# MyoWare_Proto_Shield.net
KiCad netlist of a schematic drawn in EAGLE
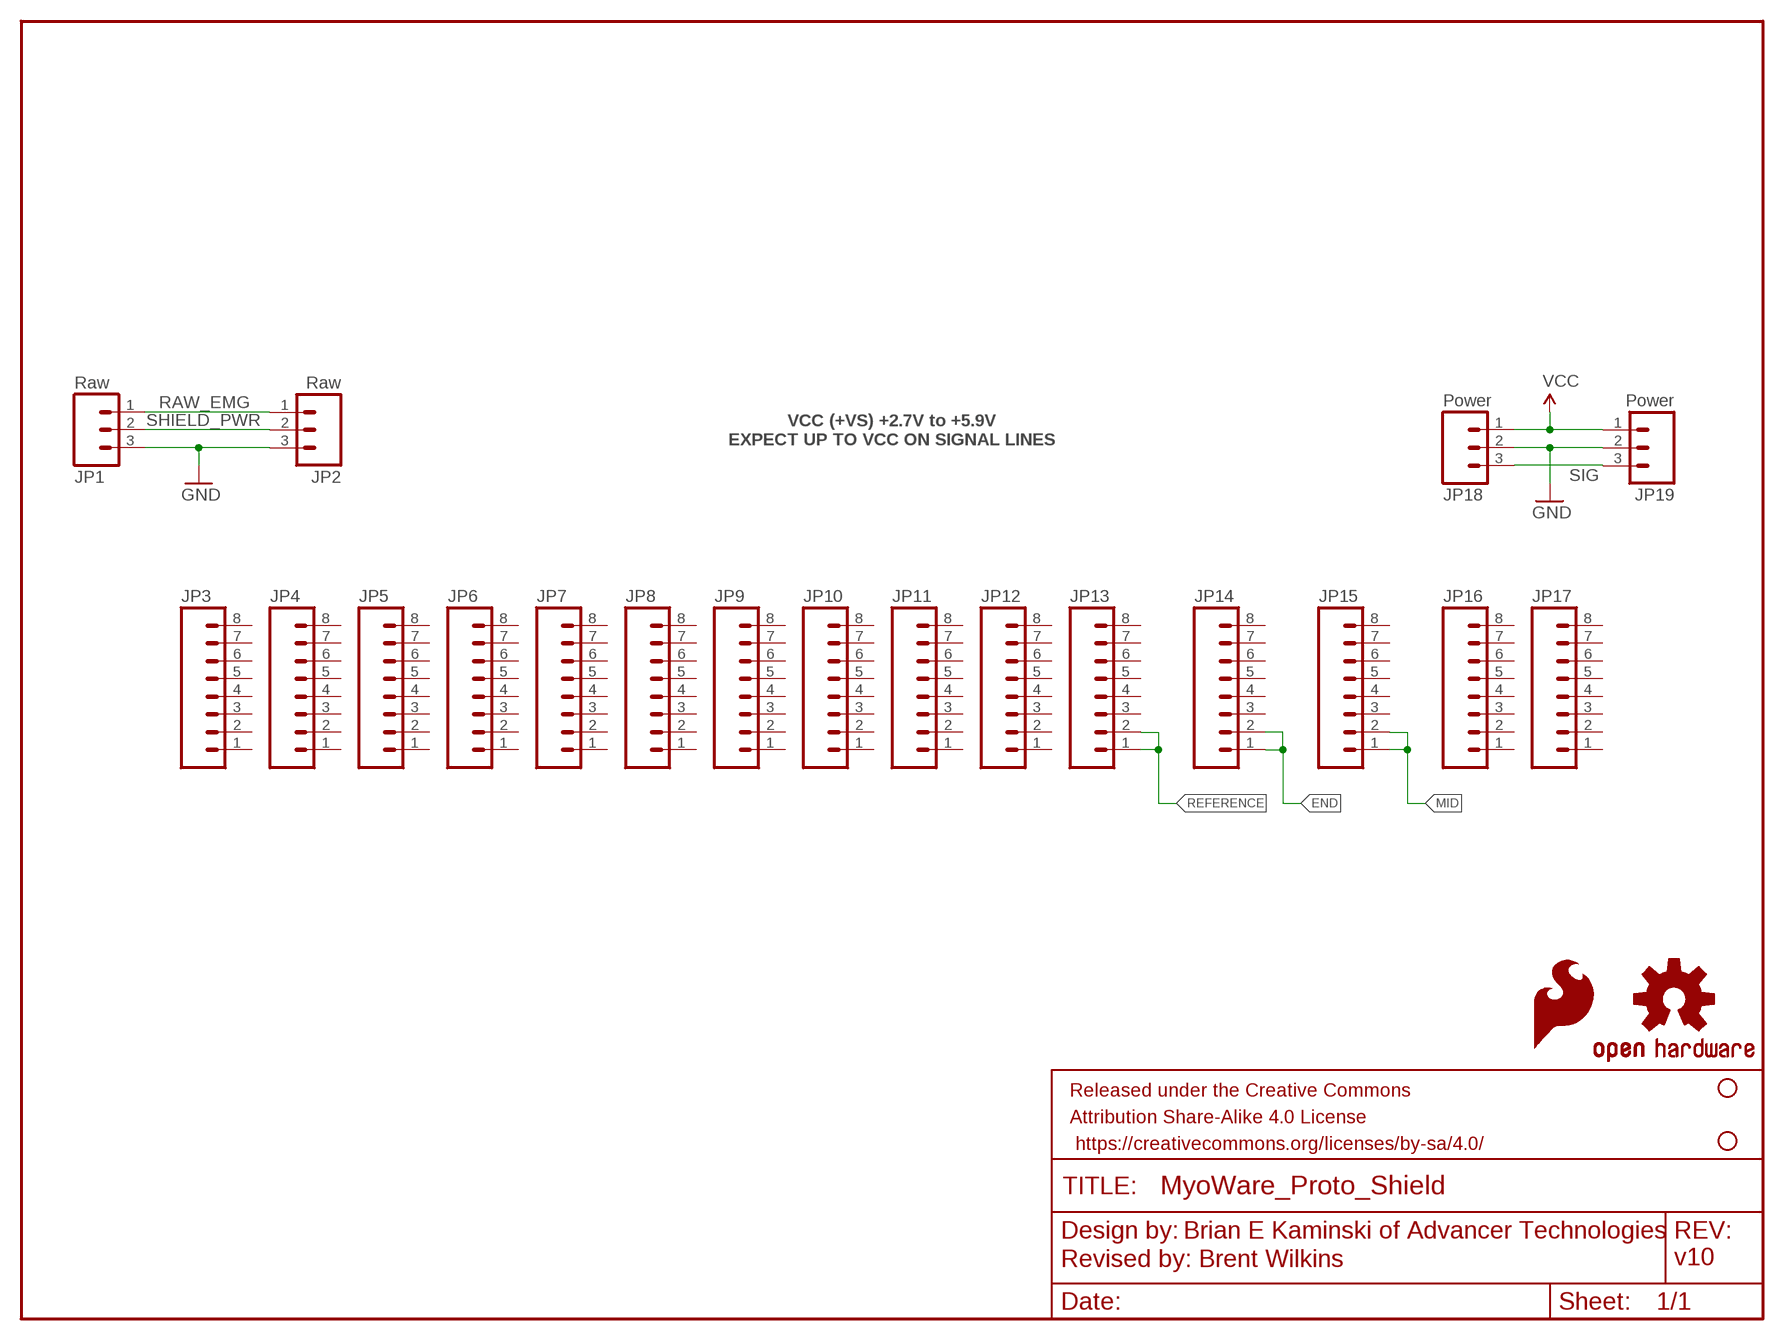
[diagram p0: schematic, sheet 1]

(export (version "E")
  (design (tool "Eeschema 10.0.6"))
  (components
    (comp (ref "FRAME1")
      (value "FRAME-LETTER")
      (footprint "eagle-import:CREATIVE_COMMONS")
      (libsource (lib "eagle-import") (part "FRAME-LETTER"))
    )
    (comp (ref "JP1")
      (value "Raw")
      (footprint "eagle-import:1X03_NO_SILK")
      (libsource (lib "eagle-import") (part "M031X03_NO_SILK"))
    )
    (comp (ref "JP2")
      (value "Raw")
      (footprint "eagle-import:1X03_NO_SILK")
      (libsource (lib "eagle-import") (part "M031X03_NO_SILK"))
    )
    (comp (ref "JP3")
      (value "M08NO_SILK")
      (footprint "eagle-import:1X08_NO_SILK")
      (libsource (lib "eagle-import") (part "M08NO_SILK"))
    )
    (comp (ref "JP4")
      (value "M08NO_SILK")
      (footprint "eagle-import:1X08_NO_SILK")
      (libsource (lib "eagle-import") (part "M08NO_SILK"))
    )
    (comp (ref "JP5")
      (value "M08NO_SILK")
      (footprint "eagle-import:1X08_NO_SILK")
      (libsource (lib "eagle-import") (part "M08NO_SILK"))
    )
    (comp (ref "JP6")
      (value "M08NO_SILK")
      (footprint "eagle-import:1X08_NO_SILK")
      (libsource (lib "eagle-import") (part "M08NO_SILK"))
    )
    (comp (ref "JP7")
      (value "M08NO_SILK")
      (footprint "eagle-import:1X08_NO_SILK")
      (libsource (lib "eagle-import") (part "M08NO_SILK"))
    )
    (comp (ref "JP8")
      (value "M08NO_SILK")
      (footprint "eagle-import:1X08_NO_SILK")
      (libsource (lib "eagle-import") (part "M08NO_SILK"))
    )
    (comp (ref "JP9")
      (value "M08NO_SILK")
      (footprint "eagle-import:1X08_NO_SILK")
      (libsource (lib "eagle-import") (part "M08NO_SILK"))
    )
    (comp (ref "JP10")
      (value "M08NO_SILK")
      (footprint "eagle-import:1X08_NO_SILK")
      (libsource (lib "eagle-import") (part "M08NO_SILK"))
    )
    (comp (ref "JP11")
      (value "M08NO_SILK")
      (footprint "eagle-import:1X08_NO_SILK")
      (libsource (lib "eagle-import") (part "M08NO_SILK"))
    )
    (comp (ref "JP12")
      (value "M08NO_SILK")
      (footprint "eagle-import:1X08_NO_SILK")
      (libsource (lib "eagle-import") (part "M08NO_SILK"))
    )
    (comp (ref "JP13")
      (value "M08NO_SILK")
      (footprint "eagle-import:1X08_NO_SILK")
      (libsource (lib "eagle-import") (part "M08NO_SILK"))
    )
    (comp (ref "JP14")
      (value "M08NO_SILK")
      (footprint "eagle-import:1X08_NO_SILK")
      (libsource (lib "eagle-import") (part "M08NO_SILK"))
    )
    (comp (ref "JP15")
      (value "M08NO_SILK")
      (footprint "eagle-import:1X08_NO_SILK")
      (libsource (lib "eagle-import") (part "M08NO_SILK"))
    )
    (comp (ref "JP16")
      (value "M08NO_SILK")
      (footprint "eagle-import:1X08_NO_SILK")
      (libsource (lib "eagle-import") (part "M08NO_SILK"))
    )
    (comp (ref "JP17")
      (value "M08NO_SILK")
      (footprint "eagle-import:1X08_NO_SILK")
      (libsource (lib "eagle-import") (part "M08NO_SILK"))
    )
    (comp (ref "JP18")
      (value "Power")
      (footprint "eagle-import:1X03_NO_SILK")
      (libsource (lib "eagle-import") (part "M031X03_NO_SILK"))
    )
    (comp (ref "JP19")
      (value "Power")
      (footprint "eagle-import:1X03_NO_SILK")
      (libsource (lib "eagle-import") (part "M031X03_NO_SILK"))
    )
    (comp (ref "JP20")
      (value "STAND-OFF")
      (footprint "eagle-import:STAND-OFF")
      (libsource (lib "eagle-import") (part "STAND-OFF"))
    )
    (comp (ref "JP21")
      (value "STAND-OFF")
      (footprint "eagle-import:STAND-OFF")
      (libsource (lib "eagle-import") (part "STAND-OFF"))
    )
    (comp (ref "LOGO1")
      (value "SFE_LOGO_FLAME.1_INCH")
      (footprint "eagle-import:SFE_LOGO_FLAME_.1")
      (libsource (lib "eagle-import") (part "SFE_LOGO_FLAME.1_INCH"))
    )
    (comp (ref "LOGO2")
      (value "OSHW-LOGOS")
      (footprint "eagle-import:OSHW-LOGO-S")
      (libsource (lib "eagle-import") (part "OSHW-LOGOS"))
    )
  )
  (nets
    (net (code "1") (name "/RAW_EMG") (class "Default")
      (node (ref "JP1") (pin "1") (pinfunction "1_1") (pintype "passive"))
      (node (ref "JP2") (pin "1") (pinfunction "1_1") (pintype "passive"))
    )
    (net (code "2") (name "/SHIELD_PWR") (class "Default")
      (node (ref "JP1") (pin "2") (pinfunction "2_2") (pintype "passive"))
      (node (ref "JP2") (pin "2") (pinfunction "2_2") (pintype "passive"))
    )
    (net (code "3") (name "/SIG") (class "Default")
      (node (ref "JP18") (pin "3") (pinfunction "3_3") (pintype "passive"))
      (node (ref "JP19") (pin "3") (pinfunction "3_3") (pintype "passive"))
    )
    (net (code "4") (name "END") (class "Default")
      (node (ref "JP14") (pin "1") (pinfunction "1_1") (pintype "passive"))
      (node (ref "JP14") (pin "2") (pinfunction "2_2") (pintype "passive"))
    )
    (net (code "5") (name "GND") (class "Default")
      (node (ref "JP1") (pin "3") (pinfunction "3_3") (pintype "passive"))
      (node (ref "JP18") (pin "2") (pinfunction "2_2") (pintype "passive"))
      (node (ref "JP19") (pin "2") (pinfunction "2_2") (pintype "passive"))
      (node (ref "JP2") (pin "3") (pinfunction "3_3") (pintype "passive"))
    )
    (net (code "6") (name "MID") (class "Default")
      (node (ref "JP15") (pin "1") (pinfunction "1_1") (pintype "passive"))
      (node (ref "JP15") (pin "2") (pinfunction "2_2") (pintype "passive"))
    )
    (net (code "7") (name "REFERENCE") (class "Default")
      (node (ref "JP13") (pin "1") (pinfunction "1_1") (pintype "passive"))
      (node (ref "JP13") (pin "2") (pinfunction "2_2") (pintype "passive"))
    )
    (net (code "8") (name "VCC") (class "Default")
      (node (ref "JP18") (pin "1") (pinfunction "1_1") (pintype "passive"))
      (node (ref "JP19") (pin "1") (pinfunction "1_1") (pintype "passive"))
    )
    (net (code "9") (name "unconnected-(JP3-Pad1)") (class "Default")
      (node (ref "JP3") (pin "1") (pinfunction "1_1") (pintype "passive"))
    )
    (net (code "10") (name "unconnected-(JP3-Pad2)") (class "Default")
      (node (ref "JP3") (pin "2") (pinfunction "2_2") (pintype "passive"))
    )
    (net (code "11") (name "unconnected-(JP3-Pad3)") (class "Default")
      (node (ref "JP3") (pin "3") (pinfunction "3_3") (pintype "passive"))
    )
    (net (code "12") (name "unconnected-(JP3-Pad4)") (class "Default")
      (node (ref "JP3") (pin "4") (pinfunction "4_4") (pintype "passive"))
    )
    (net (code "13") (name "unconnected-(JP3-Pad5)") (class "Default")
      (node (ref "JP3") (pin "5") (pinfunction "5_5") (pintype "passive"))
    )
    (net (code "14") (name "unconnected-(JP3-Pad6)") (class "Default")
      (node (ref "JP3") (pin "6") (pinfunction "6_6") (pintype "passive"))
    )
    (net (code "15") (name "unconnected-(JP3-Pad7)") (class "Default")
      (node (ref "JP3") (pin "7") (pinfunction "7_7") (pintype "passive"))
    )
    (net (code "16") (name "unconnected-(JP3-Pad8)") (class "Default")
      (node (ref "JP3") (pin "8") (pinfunction "8_8") (pintype "passive"))
    )
    (net (code "17") (name "unconnected-(JP4-Pad1)") (class "Default")
      (node (ref "JP4") (pin "1") (pinfunction "1_1") (pintype "passive"))
    )
    (net (code "18") (name "unconnected-(JP4-Pad2)") (class "Default")
      (node (ref "JP4") (pin "2") (pinfunction "2_2") (pintype "passive"))
    )
    (net (code "19") (name "unconnected-(JP4-Pad3)") (class "Default")
      (node (ref "JP4") (pin "3") (pinfunction "3_3") (pintype "passive"))
    )
    (net (code "20") (name "unconnected-(JP4-Pad4)") (class "Default")
      (node (ref "JP4") (pin "4") (pinfunction "4_4") (pintype "passive"))
    )
    (net (code "21") (name "unconnected-(JP4-Pad5)") (class "Default")
      (node (ref "JP4") (pin "5") (pinfunction "5_5") (pintype "passive"))
    )
    (net (code "22") (name "unconnected-(JP4-Pad6)") (class "Default")
      (node (ref "JP4") (pin "6") (pinfunction "6_6") (pintype "passive"))
    )
    (net (code "23") (name "unconnected-(JP4-Pad7)") (class "Default")
      (node (ref "JP4") (pin "7") (pinfunction "7_7") (pintype "passive"))
    )
    (net (code "24") (name "unconnected-(JP4-Pad8)") (class "Default")
      (node (ref "JP4") (pin "8") (pinfunction "8_8") (pintype "passive"))
    )
    (net (code "25") (name "unconnected-(JP5-Pad1)") (class "Default")
      (node (ref "JP5") (pin "1") (pinfunction "1_1") (pintype "passive"))
    )
    (net (code "26") (name "unconnected-(JP5-Pad2)") (class "Default")
      (node (ref "JP5") (pin "2") (pinfunction "2_2") (pintype "passive"))
    )
    (net (code "27") (name "unconnected-(JP5-Pad3)") (class "Default")
      (node (ref "JP5") (pin "3") (pinfunction "3_3") (pintype "passive"))
    )
    (net (code "28") (name "unconnected-(JP5-Pad4)") (class "Default")
      (node (ref "JP5") (pin "4") (pinfunction "4_4") (pintype "passive"))
    )
    (net (code "29") (name "unconnected-(JP5-Pad5)") (class "Default")
      (node (ref "JP5") (pin "5") (pinfunction "5_5") (pintype "passive"))
    )
    (net (code "30") (name "unconnected-(JP5-Pad6)") (class "Default")
      (node (ref "JP5") (pin "6") (pinfunction "6_6") (pintype "passive"))
    )
    (net (code "31") (name "unconnected-(JP5-Pad7)") (class "Default")
      (node (ref "JP5") (pin "7") (pinfunction "7_7") (pintype "passive"))
    )
    (net (code "32") (name "unconnected-(JP5-Pad8)") (class "Default")
      (node (ref "JP5") (pin "8") (pinfunction "8_8") (pintype "passive"))
    )
    (net (code "33") (name "unconnected-(JP6-Pad1)") (class "Default")
      (node (ref "JP6") (pin "1") (pinfunction "1_1") (pintype "passive"))
    )
    (net (code "34") (name "unconnected-(JP6-Pad2)") (class "Default")
      (node (ref "JP6") (pin "2") (pinfunction "2_2") (pintype "passive"))
    )
    (net (code "35") (name "unconnected-(JP6-Pad3)") (class "Default")
      (node (ref "JP6") (pin "3") (pinfunction "3_3") (pintype "passive"))
    )
    (net (code "36") (name "unconnected-(JP6-Pad4)") (class "Default")
      (node (ref "JP6") (pin "4") (pinfunction "4_4") (pintype "passive"))
    )
    (net (code "37") (name "unconnected-(JP6-Pad5)") (class "Default")
      (node (ref "JP6") (pin "5") (pinfunction "5_5") (pintype "passive"))
    )
    (net (code "38") (name "unconnected-(JP6-Pad6)") (class "Default")
      (node (ref "JP6") (pin "6") (pinfunction "6_6") (pintype "passive"))
    )
    (net (code "39") (name "unconnected-(JP6-Pad7)") (class "Default")
      (node (ref "JP6") (pin "7") (pinfunction "7_7") (pintype "passive"))
    )
    (net (code "40") (name "unconnected-(JP6-Pad8)") (class "Default")
      (node (ref "JP6") (pin "8") (pinfunction "8_8") (pintype "passive"))
    )
    (net (code "41") (name "unconnected-(JP7-Pad1)") (class "Default")
      (node (ref "JP7") (pin "1") (pinfunction "1_1") (pintype "passive"))
    )
    (net (code "42") (name "unconnected-(JP7-Pad2)") (class "Default")
      (node (ref "JP7") (pin "2") (pinfunction "2_2") (pintype "passive"))
    )
    (net (code "43") (name "unconnected-(JP7-Pad3)") (class "Default")
      (node (ref "JP7") (pin "3") (pinfunction "3_3") (pintype "passive"))
    )
    (net (code "44") (name "unconnected-(JP7-Pad4)") (class "Default")
      (node (ref "JP7") (pin "4") (pinfunction "4_4") (pintype "passive"))
    )
    (net (code "45") (name "unconnected-(JP7-Pad5)") (class "Default")
      (node (ref "JP7") (pin "5") (pinfunction "5_5") (pintype "passive"))
    )
    (net (code "46") (name "unconnected-(JP7-Pad6)") (class "Default")
      (node (ref "JP7") (pin "6") (pinfunction "6_6") (pintype "passive"))
    )
    (net (code "47") (name "unconnected-(JP7-Pad7)") (class "Default")
      (node (ref "JP7") (pin "7") (pinfunction "7_7") (pintype "passive"))
    )
    (net (code "48") (name "unconnected-(JP7-Pad8)") (class "Default")
      (node (ref "JP7") (pin "8") (pinfunction "8_8") (pintype "passive"))
    )
    (net (code "49") (name "unconnected-(JP8-Pad1)") (class "Default")
      (node (ref "JP8") (pin "1") (pinfunction "1_1") (pintype "passive"))
    )
    (net (code "50") (name "unconnected-(JP8-Pad2)") (class "Default")
      (node (ref "JP8") (pin "2") (pinfunction "2_2") (pintype "passive"))
    )
    (net (code "51") (name "unconnected-(JP8-Pad3)") (class "Default")
      (node (ref "JP8") (pin "3") (pinfunction "3_3") (pintype "passive"))
    )
    (net (code "52") (name "unconnected-(JP8-Pad4)") (class "Default")
      (node (ref "JP8") (pin "4") (pinfunction "4_4") (pintype "passive"))
    )
    (net (code "53") (name "unconnected-(JP8-Pad5)") (class "Default")
      (node (ref "JP8") (pin "5") (pinfunction "5_5") (pintype "passive"))
    )
    (net (code "54") (name "unconnected-(JP8-Pad6)") (class "Default")
      (node (ref "JP8") (pin "6") (pinfunction "6_6") (pintype "passive"))
    )
    (net (code "55") (name "unconnected-(JP8-Pad7)") (class "Default")
      (node (ref "JP8") (pin "7") (pinfunction "7_7") (pintype "passive"))
    )
    (net (code "56") (name "unconnected-(JP8-Pad8)") (class "Default")
      (node (ref "JP8") (pin "8") (pinfunction "8_8") (pintype "passive"))
    )
    (net (code "57") (name "unconnected-(JP9-Pad1)") (class "Default")
      (node (ref "JP9") (pin "1") (pinfunction "1_1") (pintype "passive"))
    )
    (net (code "58") (name "unconnected-(JP9-Pad2)") (class "Default")
      (node (ref "JP9") (pin "2") (pinfunction "2_2") (pintype "passive"))
    )
    (net (code "59") (name "unconnected-(JP9-Pad3)") (class "Default")
      (node (ref "JP9") (pin "3") (pinfunction "3_3") (pintype "passive"))
    )
    (net (code "60") (name "unconnected-(JP9-Pad4)") (class "Default")
      (node (ref "JP9") (pin "4") (pinfunction "4_4") (pintype "passive"))
    )
    (net (code "61") (name "unconnected-(JP9-Pad5)") (class "Default")
      (node (ref "JP9") (pin "5") (pinfunction "5_5") (pintype "passive"))
    )
    (net (code "62") (name "unconnected-(JP9-Pad6)") (class "Default")
      (node (ref "JP9") (pin "6") (pinfunction "6_6") (pintype "passive"))
    )
    (net (code "63") (name "unconnected-(JP9-Pad7)") (class "Default")
      (node (ref "JP9") (pin "7") (pinfunction "7_7") (pintype "passive"))
    )
    (net (code "64") (name "unconnected-(JP9-Pad8)") (class "Default")
      (node (ref "JP9") (pin "8") (pinfunction "8_8") (pintype "passive"))
    )
    (net (code "65") (name "unconnected-(JP10-Pad1)") (class "Default")
      (node (ref "JP10") (pin "1") (pinfunction "1_1") (pintype "passive"))
    )
    (net (code "66") (name "unconnected-(JP10-Pad2)") (class "Default")
      (node (ref "JP10") (pin "2") (pinfunction "2_2") (pintype "passive"))
    )
    (net (code "67") (name "unconnected-(JP10-Pad3)") (class "Default")
      (node (ref "JP10") (pin "3") (pinfunction "3_3") (pintype "passive"))
    )
    (net (code "68") (name "unconnected-(JP10-Pad4)") (class "Default")
      (node (ref "JP10") (pin "4") (pinfunction "4_4") (pintype "passive"))
    )
    (net (code "69") (name "unconnected-(JP10-Pad5)") (class "Default")
      (node (ref "JP10") (pin "5") (pinfunction "5_5") (pintype "passive"))
    )
    (net (code "70") (name "unconnected-(JP10-Pad6)") (class "Default")
      (node (ref "JP10") (pin "6") (pinfunction "6_6") (pintype "passive"))
    )
    (net (code "71") (name "unconnected-(JP10-Pad7)") (class "Default")
      (node (ref "JP10") (pin "7") (pinfunction "7_7") (pintype "passive"))
    )
    (net (code "72") (name "unconnected-(JP10-Pad8)") (class "Default")
      (node (ref "JP10") (pin "8") (pinfunction "8_8") (pintype "passive"))
    )
    (net (code "73") (name "unconnected-(JP11-Pad1)") (class "Default")
      (node (ref "JP11") (pin "1") (pinfunction "1_1") (pintype "passive"))
    )
    (net (code "74") (name "unconnected-(JP11-Pad2)") (class "Default")
      (node (ref "JP11") (pin "2") (pinfunction "2_2") (pintype "passive"))
    )
    (net (code "75") (name "unconnected-(JP11-Pad3)") (class "Default")
      (node (ref "JP11") (pin "3") (pinfunction "3_3") (pintype "passive"))
    )
    (net (code "76") (name "unconnected-(JP11-Pad4)") (class "Default")
      (node (ref "JP11") (pin "4") (pinfunction "4_4") (pintype "passive"))
    )
    (net (code "77") (name "unconnected-(JP11-Pad5)") (class "Default")
      (node (ref "JP11") (pin "5") (pinfunction "5_5") (pintype "passive"))
    )
    (net (code "78") (name "unconnected-(JP11-Pad6)") (class "Default")
      (node (ref "JP11") (pin "6") (pinfunction "6_6") (pintype "passive"))
    )
    (net (code "79") (name "unconnected-(JP11-Pad7)") (class "Default")
      (node (ref "JP11") (pin "7") (pinfunction "7_7") (pintype "passive"))
    )
    (net (code "80") (name "unconnected-(JP11-Pad8)") (class "Default")
      (node (ref "JP11") (pin "8") (pinfunction "8_8") (pintype "passive"))
    )
    (net (code "81") (name "unconnected-(JP12-Pad1)") (class "Default")
      (node (ref "JP12") (pin "1") (pinfunction "1_1") (pintype "passive"))
    )
    (net (code "82") (name "unconnected-(JP12-Pad2)") (class "Default")
      (node (ref "JP12") (pin "2") (pinfunction "2_2") (pintype "passive"))
    )
    (net (code "83") (name "unconnected-(JP12-Pad3)") (class "Default")
      (node (ref "JP12") (pin "3") (pinfunction "3_3") (pintype "passive"))
    )
    (net (code "84") (name "unconnected-(JP12-Pad4)") (class "Default")
      (node (ref "JP12") (pin "4") (pinfunction "4_4") (pintype "passive"))
    )
    (net (code "85") (name "unconnected-(JP12-Pad5)") (class "Default")
      (node (ref "JP12") (pin "5") (pinfunction "5_5") (pintype "passive"))
    )
    (net (code "86") (name "unconnected-(JP12-Pad6)") (class "Default")
      (node (ref "JP12") (pin "6") (pinfunction "6_6") (pintype "passive"))
    )
    (net (code "87") (name "unconnected-(JP12-Pad7)") (class "Default")
      (node (ref "JP12") (pin "7") (pinfunction "7_7") (pintype "passive"))
    )
    (net (code "88") (name "unconnected-(JP12-Pad8)") (class "Default")
      (node (ref "JP12") (pin "8") (pinfunction "8_8") (pintype "passive"))
    )
    (net (code "89") (name "unconnected-(JP13-Pad3)") (class "Default")
      (node (ref "JP13") (pin "3") (pinfunction "3_3") (pintype "passive"))
    )
    (net (code "90") (name "unconnected-(JP13-Pad4)") (class "Default")
      (node (ref "JP13") (pin "4") (pinfunction "4_4") (pintype "passive"))
    )
    (net (code "91") (name "unconnected-(JP13-Pad5)") (class "Default")
      (node (ref "JP13") (pin "5") (pinfunction "5_5") (pintype "passive"))
    )
    (net (code "92") (name "unconnected-(JP13-Pad6)") (class "Default")
      (node (ref "JP13") (pin "6") (pinfunction "6_6") (pintype "passive"))
    )
    (net (code "93") (name "unconnected-(JP13-Pad7)") (class "Default")
      (node (ref "JP13") (pin "7") (pinfunction "7_7") (pintype "passive"))
    )
    (net (code "94") (name "unconnected-(JP13-Pad8)") (class "Default")
      (node (ref "JP13") (pin "8") (pinfunction "8_8") (pintype "passive"))
    )
    (net (code "95") (name "unconnected-(JP14-Pad3)") (class "Default")
      (node (ref "JP14") (pin "3") (pinfunction "3_3") (pintype "passive"))
    )
    (net (code "96") (name "unconnected-(JP14-Pad4)") (class "Default")
      (node (ref "JP14") (pin "4") (pinfunction "4_4") (pintype "passive"))
    )
    (net (code "97") (name "unconnected-(JP14-Pad5)") (class "Default")
      (node (ref "JP14") (pin "5") (pinfunction "5_5") (pintype "passive"))
    )
    (net (code "98") (name "unconnected-(JP14-Pad6)") (class "Default")
      (node (ref "JP14") (pin "6") (pinfunction "6_6") (pintype "passive"))
    )
    (net (code "99") (name "unconnected-(JP14-Pad7)") (class "Default")
      (node (ref "JP14") (pin "7") (pinfunction "7_7") (pintype "passive"))
    )
    (net (code "100") (name "unconnected-(JP14-Pad8)") (class "Default")
      (node (ref "JP14") (pin "8") (pinfunction "8_8") (pintype "passive"))
    )
    (net (code "101") (name "unconnected-(JP15-Pad3)") (class "Default")
      (node (ref "JP15") (pin "3") (pinfunction "3_3") (pintype "passive"))
    )
    (net (code "102") (name "unconnected-(JP15-Pad4)") (class "Default")
      (node (ref "JP15") (pin "4") (pinfunction "4_4") (pintype "passive"))
    )
    (net (code "103") (name "unconnected-(JP15-Pad5)") (class "Default")
      (node (ref "JP15") (pin "5") (pinfunction "5_5") (pintype "passive"))
    )
    (net (code "104") (name "unconnected-(JP15-Pad6)") (class "Default")
      (node (ref "JP15") (pin "6") (pinfunction "6_6") (pintype "passive"))
    )
    (net (code "105") (name "unconnected-(JP15-Pad7)") (class "Default")
      (node (ref "JP15") (pin "7") (pinfunction "7_7") (pintype "passive"))
    )
    (net (code "106") (name "unconnected-(JP15-Pad8)") (class "Default")
      (node (ref "JP15") (pin "8") (pinfunction "8_8") (pintype "passive"))
    )
    (net (code "107") (name "unconnected-(JP16-Pad1)") (class "Default")
      (node (ref "JP16") (pin "1") (pinfunction "1_1") (pintype "passive"))
    )
    (net (code "108") (name "unconnected-(JP16-Pad2)") (class "Default")
      (node (ref "JP16") (pin "2") (pinfunction "2_2") (pintype "passive"))
    )
    (net (code "109") (name "unconnected-(JP16-Pad3)") (class "Default")
      (node (ref "JP16") (pin "3") (pinfunction "3_3") (pintype "passive"))
    )
    (net (code "110") (name "unconnected-(JP16-Pad4)") (class "Default")
      (node (ref "JP16") (pin "4") (pinfunction "4_4") (pintype "passive"))
    )
    (net (code "111") (name "unconnected-(JP16-Pad5)") (class "Default")
      (node (ref "JP16") (pin "5") (pinfunction "5_5") (pintype "passive"))
    )
    (net (code "112") (name "unconnected-(JP16-Pad6)") (class "Default")
      (node (ref "JP16") (pin "6") (pinfunction "6_6") (pintype "passive"))
    )
    (net (code "113") (name "unconnected-(JP16-Pad7)") (class "Default")
      (node (ref "JP16") (pin "7") (pinfunction "7_7") (pintype "passive"))
    )
    (net (code "114") (name "unconnected-(JP16-Pad8)") (class "Default")
      (node (ref "JP16") (pin "8") (pinfunction "8_8") (pintype "passive"))
    )
    (net (code "115") (name "unconnected-(JP17-Pad1)") (class "Default")
      (node (ref "JP17") (pin "1") (pinfunction "1_1") (pintype "passive"))
    )
    (net (code "116") (name "unconnected-(JP17-Pad2)") (class "Default")
      (node (ref "JP17") (pin "2") (pinfunction "2_2") (pintype "passive"))
    )
    (net (code "117") (name "unconnected-(JP17-Pad3)") (class "Default")
      (node (ref "JP17") (pin "3") (pinfunction "3_3") (pintype "passive"))
    )
    (net (code "118") (name "unconnected-(JP17-Pad4)") (class "Default")
      (node (ref "JP17") (pin "4") (pinfunction "4_4") (pintype "passive"))
    )
    (net (code "119") (name "unconnected-(JP17-Pad5)") (class "Default")
      (node (ref "JP17") (pin "5") (pinfunction "5_5") (pintype "passive"))
    )
    (net (code "120") (name "unconnected-(JP17-Pad6)") (class "Default")
      (node (ref "JP17") (pin "6") (pinfunction "6_6") (pintype "passive"))
    )
    (net (code "121") (name "unconnected-(JP17-Pad7)") (class "Default")
      (node (ref "JP17") (pin "7") (pinfunction "7_7") (pintype "passive"))
    )
    (net (code "122") (name "unconnected-(JP17-Pad8)") (class "Default")
      (node (ref "JP17") (pin "8") (pinfunction "8_8") (pintype "passive"))
    )
  )
)
